# Prototype_PCB.net
KiCad netlist of a schematic drawn in Altium Designer
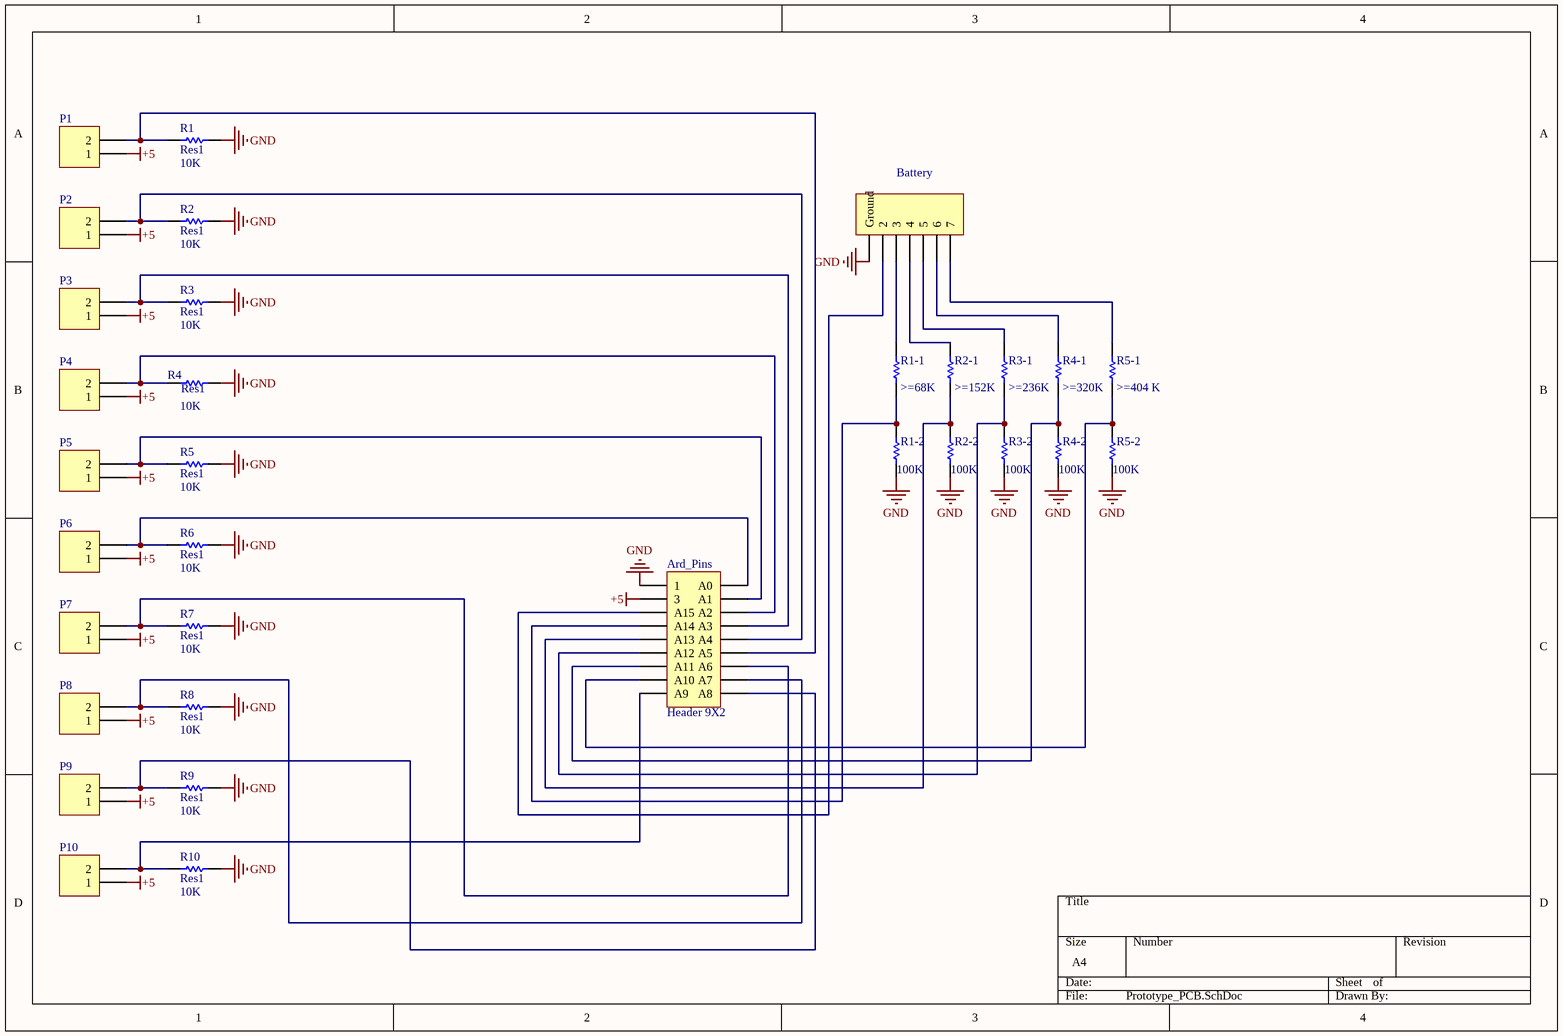
[diagram p0: Prototype_PCB.SchDoc]

(export (version "E")
  (design (tool "Eeschema 10.0.6"))
  (components
    (comp (ref "Ard_Pins")
      (value "Header 9X2")
      (footprint "HDR2X9")
      (description "Header, 9-Pin, Dual row")
      (fields (field (name "PUBLISHER") "Altium Limited"))
      (libsource (lib "Miscellaneous Connectors") (part "Header 9X2"))
    )
    (comp (ref "Battery")
      (value "1")
      (footprint "HDR1X7")
      (description "Header, 7-Pin")
      (fields (field (name "PUBLISHER") "Altium Limited"))
      (libsource (lib "Miscellaneous Connectors") (part "Header 7"))
    )
    (comp (ref "P1")
      (value "MHDR1X2")
      (footprint "MHDR1X2")
      (description "Header, 2-Pin")
      (fields (field (name "PUBLISHER") "Altium Limited"))
      (libsource (lib "Miscellaneous Connectors") (part "MHDR1X2"))
    )
    (comp (ref "P2")
      (value "MHDR1X2")
      (footprint "MHDR1X2")
      (description "Header, 2-Pin")
      (fields (field (name "PUBLISHER") "Altium Limited"))
      (libsource (lib "Miscellaneous Connectors") (part "MHDR1X2"))
    )
    (comp (ref "P3")
      (value "MHDR1X2")
      (footprint "MHDR1X2")
      (description "Header, 2-Pin")
      (fields (field (name "PUBLISHER") "Altium Limited"))
      (libsource (lib "Miscellaneous Connectors") (part "MHDR1X2"))
    )
    (comp (ref "P4")
      (value "MHDR1X2")
      (footprint "MHDR1X2")
      (description "Header, 2-Pin")
      (fields (field (name "PUBLISHER") "Altium Limited"))
      (libsource (lib "Miscellaneous Connectors") (part "MHDR1X2"))
    )
    (comp (ref "P5")
      (value "MHDR1X2")
      (footprint "MHDR1X2")
      (description "Header, 2-Pin")
      (fields (field (name "PUBLISHER") "Altium Limited"))
      (libsource (lib "Miscellaneous Connectors") (part "MHDR1X2"))
    )
    (comp (ref "P6")
      (value "MHDR1X2")
      (footprint "MHDR1X2")
      (description "Header, 2-Pin")
      (fields (field (name "PUBLISHER") "Altium Limited"))
      (libsource (lib "Miscellaneous Connectors") (part "MHDR1X2"))
    )
    (comp (ref "P7")
      (value "MHDR1X2")
      (footprint "MHDR1X2")
      (description "Header, 2-Pin")
      (fields (field (name "PUBLISHER") "Altium Limited"))
      (libsource (lib "Miscellaneous Connectors") (part "MHDR1X2"))
    )
    (comp (ref "P8")
      (value "MHDR1X2")
      (footprint "MHDR1X2")
      (description "Header, 2-Pin")
      (fields (field (name "PUBLISHER") "Altium Limited"))
      (libsource (lib "Miscellaneous Connectors") (part "MHDR1X2"))
    )
    (comp (ref "P9")
      (value "MHDR1X2")
      (footprint "MHDR1X2")
      (description "Header, 2-Pin")
      (fields (field (name "PUBLISHER") "Altium Limited"))
      (libsource (lib "Miscellaneous Connectors") (part "MHDR1X2"))
    )
    (comp (ref "P10")
      (value "MHDR1X2")
      (footprint "MHDR1X2")
      (description "Header, 2-Pin")
      (fields (field (name "PUBLISHER") "Altium Limited"))
      (libsource (lib "Miscellaneous Connectors") (part "MHDR1X2"))
    )
    (comp (ref "R1")
      (value "Res1")
      (footprint "AXIAL-0.3")
      (description "Resistor")
      (fields (field (name "ALTIUM_VALUE") "10K") (field (name "PUBLISHER") "Altium Limited"))
      (libsource (lib "Miscellaneous Devices") (part "Res1"))
    )
    (comp (ref "R1-1")
      (value ">=68K")
      (footprint "AXIAL-0.3")
      (description "Resistor")
      (fields (field (name "Comment") "Res1") (field (name "PUBLISHER") "Altium Limited"))
      (libsource (lib "Miscellaneous Devices") (part "Res1"))
    )
    (comp (ref "R1-2")
      (value "100K")
      (footprint "AXIAL-0.3")
      (description "Resistor")
      (fields (field (name "Comment") "Res1") (field (name "PUBLISHER") "Altium Limited"))
      (libsource (lib "Miscellaneous Devices") (part "Res1"))
    )
    (comp (ref "R2")
      (value "Res1")
      (footprint "AXIAL-0.3")
      (description "Resistor")
      (fields (field (name "ALTIUM_VALUE") "10K") (field (name "PUBLISHER") "Altium Limited"))
      (libsource (lib "Miscellaneous Devices") (part "Res1"))
    )
    (comp (ref "R2-1")
      (value ">=152K")
      (footprint "AXIAL-0.3")
      (description "Resistor")
      (fields (field (name "Comment") "Res1") (field (name "PUBLISHER") "Altium Limited"))
      (libsource (lib "Miscellaneous Devices") (part "Res1"))
    )
    (comp (ref "R2-2")
      (value "100K")
      (footprint "AXIAL-0.3")
      (description "Resistor")
      (fields (field (name "Comment") "Res1") (field (name "PUBLISHER") "Altium Limited"))
      (libsource (lib "Miscellaneous Devices") (part "Res1"))
    )
    (comp (ref "R3")
      (value "Res1")
      (footprint "AXIAL-0.3")
      (description "Resistor")
      (fields (field (name "ALTIUM_VALUE") "10K") (field (name "PUBLISHER") "Altium Limited"))
      (libsource (lib "Miscellaneous Devices") (part "Res1"))
    )
    (comp (ref "R3-1")
      (value ">=236K")
      (footprint "AXIAL-0.3")
      (description "Resistor")
      (fields (field (name "Comment") "Res1") (field (name "PUBLISHER") "Altium Limited"))
      (libsource (lib "Miscellaneous Devices") (part "Res1"))
    )
    (comp (ref "R3-2")
      (value "100K")
      (footprint "AXIAL-0.3")
      (description "Resistor")
      (fields (field (name "Comment") "Res1") (field (name "PUBLISHER") "Altium Limited"))
      (libsource (lib "Miscellaneous Devices") (part "Res1"))
    )
    (comp (ref "R4")
      (value "Res1")
      (footprint "AXIAL-0.3")
      (description "Resistor")
      (fields (field (name "ALTIUM_VALUE") "10K") (field (name "PUBLISHER") "Altium Limited"))
      (libsource (lib "Miscellaneous Devices") (part "Res1"))
    )
    (comp (ref "R4-1")
      (value ">=320K")
      (footprint "AXIAL-0.3")
      (description "Resistor")
      (fields (field (name "Comment") "Res1") (field (name "PUBLISHER") "Altium Limited"))
      (libsource (lib "Miscellaneous Devices") (part "Res1"))
    )
    (comp (ref "R4-2")
      (value "100K")
      (footprint "AXIAL-0.3")
      (description "Resistor")
      (fields (field (name "Comment") "Res1") (field (name "PUBLISHER") "Altium Limited"))
      (libsource (lib "Miscellaneous Devices") (part "Res1"))
    )
    (comp (ref "R5")
      (value "Res1")
      (footprint "AXIAL-0.3")
      (description "Resistor")
      (fields (field (name "ALTIUM_VALUE") "10K") (field (name "PUBLISHER") "Altium Limited"))
      (libsource (lib "Miscellaneous Devices") (part "Res1"))
    )
    (comp (ref "R5-1")
      (value ">=404 K")
      (footprint "AXIAL-0.3")
      (description "Resistor")
      (fields (field (name "Comment") "Res1") (field (name "PUBLISHER") "Altium Limited"))
      (libsource (lib "Miscellaneous Devices") (part "Res1"))
    )
    (comp (ref "R5-2")
      (value "100K")
      (footprint "AXIAL-0.3")
      (description "Resistor")
      (fields (field (name "Comment") "Res1") (field (name "PUBLISHER") "Altium Limited"))
      (libsource (lib "Miscellaneous Devices") (part "Res1"))
    )
    (comp (ref "R6")
      (value "Res1")
      (footprint "AXIAL-0.3")
      (description "Resistor")
      (fields (field (name "ALTIUM_VALUE") "10K") (field (name "PUBLISHER") "Altium Limited"))
      (libsource (lib "Miscellaneous Devices") (part "Res1"))
    )
    (comp (ref "R7")
      (value "Res1")
      (footprint "AXIAL-0.3")
      (description "Resistor")
      (fields (field (name "ALTIUM_VALUE") "10K") (field (name "PUBLISHER") "Altium Limited"))
      (libsource (lib "Miscellaneous Devices") (part "Res1"))
    )
    (comp (ref "R8")
      (value "Res1")
      (footprint "AXIAL-0.3")
      (description "Resistor")
      (fields (field (name "ALTIUM_VALUE") "10K") (field (name "PUBLISHER") "Altium Limited"))
      (libsource (lib "Miscellaneous Devices") (part "Res1"))
    )
    (comp (ref "R9")
      (value "Res1")
      (footprint "AXIAL-0.3")
      (description "Resistor")
      (fields (field (name "ALTIUM_VALUE") "10K") (field (name "PUBLISHER") "Altium Limited"))
      (libsource (lib "Miscellaneous Devices") (part "Res1"))
    )
    (comp (ref "R10")
      (value "Res1")
      (footprint "AXIAL-0.3")
      (description "Resistor")
      (fields (field (name "ALTIUM_VALUE") "10K") (field (name "PUBLISHER") "Altium Limited"))
      (libsource (lib "Miscellaneous Devices") (part "Res1"))
    )
  )
  (nets
    (net (code "1") (name "+5") (class "Default")
      (node (ref "Ard_Pins") (pin "3") (pinfunction "3_3") (pintype "passive"))
      (node (ref "P1") (pin "1") (pinfunction "1_1") (pintype "passive"))
      (node (ref "P10") (pin "1") (pinfunction "1_1") (pintype "passive"))
      (node (ref "P2") (pin "1") (pinfunction "1_1") (pintype "passive"))
      (node (ref "P3") (pin "1") (pinfunction "1_1") (pintype "passive"))
      (node (ref "P4") (pin "1") (pinfunction "1_1") (pintype "passive"))
      (node (ref "P5") (pin "1") (pinfunction "1_1") (pintype "passive"))
      (node (ref "P6") (pin "1") (pinfunction "1_1") (pintype "passive"))
      (node (ref "P7") (pin "1") (pinfunction "1_1") (pintype "passive"))
      (node (ref "P8") (pin "1") (pinfunction "1_1") (pintype "passive"))
      (node (ref "P9") (pin "1") (pinfunction "1_1") (pintype "passive"))
    )
    (net (code "2") (name "GND") (class "Default")
      (node (ref "Ard_Pins") (pin "1") (pinfunction "1_1") (pintype "passive"))
      (node (ref "Battery") (pin "1") (pinfunction "Ground_1") (pintype "passive"))
      (node (ref "R1") (pin "2") (pinfunction "2_2") (pintype "passive"))
      (node (ref "R1-2") (pin "1") (pinfunction "1_1") (pintype "passive"))
      (node (ref "R10") (pin "2") (pinfunction "2_2") (pintype "passive"))
      (node (ref "R2") (pin "2") (pinfunction "2_2") (pintype "passive"))
      (node (ref "R2-2") (pin "1") (pinfunction "1_1") (pintype "passive"))
      (node (ref "R3") (pin "2") (pinfunction "2_2") (pintype "passive"))
      (node (ref "R3-2") (pin "1") (pinfunction "1_1") (pintype "passive"))
      (node (ref "R4") (pin "2") (pinfunction "2_2") (pintype "passive"))
      (node (ref "R4-2") (pin "1") (pinfunction "1_1") (pintype "passive"))
      (node (ref "R5") (pin "2") (pinfunction "2_2") (pintype "passive"))
      (node (ref "R5-2") (pin "1") (pinfunction "1_1") (pintype "passive"))
      (node (ref "R6") (pin "2") (pinfunction "2_2") (pintype "passive"))
      (node (ref "R7") (pin "2") (pinfunction "2_2") (pintype "passive"))
      (node (ref "R8") (pin "2") (pinfunction "2_2") (pintype "passive"))
      (node (ref "R9") (pin "2") (pinfunction "2_2") (pintype "passive"))
    )
    (net (code "3") (name "Net-(Ard_Pins-A0)") (class "Default")
      (node (ref "Ard_Pins") (pin "2") (pinfunction "A0_2") (pintype "passive"))
      (node (ref "P6") (pin "2") (pinfunction "2_2") (pintype "passive"))
      (node (ref "R6") (pin "1") (pinfunction "1_1") (pintype "passive"))
    )
    (net (code "4") (name "Net-(Ard_Pins-A1)") (class "Default")
      (node (ref "Ard_Pins") (pin "4") (pinfunction "A1_4") (pintype "passive"))
      (node (ref "P5") (pin "2") (pinfunction "2_2") (pintype "passive"))
      (node (ref "R5") (pin "1") (pinfunction "1_1") (pintype "passive"))
    )
    (net (code "5") (name "Net-(Ard_Pins-A2)") (class "Default")
      (node (ref "Ard_Pins") (pin "6") (pinfunction "A2_6") (pintype "passive"))
      (node (ref "P4") (pin "2") (pinfunction "2_2") (pintype "passive"))
      (node (ref "R4") (pin "1") (pinfunction "1_1") (pintype "passive"))
    )
    (net (code "6") (name "Net-(Ard_Pins-A3)") (class "Default")
      (node (ref "Ard_Pins") (pin "8") (pinfunction "A3_8") (pintype "passive"))
      (node (ref "P3") (pin "2") (pinfunction "2_2") (pintype "passive"))
      (node (ref "R3") (pin "1") (pinfunction "1_1") (pintype "passive"))
    )
    (net (code "7") (name "Net-(Ard_Pins-A4)") (class "Default")
      (node (ref "Ard_Pins") (pin "10") (pinfunction "A4_10") (pintype "passive"))
      (node (ref "P2") (pin "2") (pinfunction "2_2") (pintype "passive"))
      (node (ref "R2") (pin "1") (pinfunction "1_1") (pintype "passive"))
    )
    (net (code "8") (name "Net-(Ard_Pins-A5)") (class "Default")
      (node (ref "Ard_Pins") (pin "12") (pinfunction "A5_12") (pintype "passive"))
      (node (ref "P1") (pin "2") (pinfunction "2_2") (pintype "passive"))
      (node (ref "R1") (pin "1") (pinfunction "1_1") (pintype "passive"))
    )
    (net (code "9") (name "Net-(Ard_Pins-A6)") (class "Default")
      (node (ref "Ard_Pins") (pin "14") (pinfunction "A6_14") (pintype "passive"))
      (node (ref "P7") (pin "2") (pinfunction "2_2") (pintype "passive"))
      (node (ref "R7") (pin "1") (pinfunction "1_1") (pintype "passive"))
    )
    (net (code "10") (name "Net-(Ard_Pins-A7)") (class "Default")
      (node (ref "Ard_Pins") (pin "16") (pinfunction "A7_16") (pintype "passive"))
      (node (ref "P8") (pin "2") (pinfunction "2_2") (pintype "passive"))
      (node (ref "R8") (pin "1") (pinfunction "1_1") (pintype "passive"))
    )
    (net (code "11") (name "Net-(Ard_Pins-A8)") (class "Default")
      (node (ref "Ard_Pins") (pin "18") (pinfunction "A8_18") (pintype "passive"))
      (node (ref "P9") (pin "2") (pinfunction "2_2") (pintype "passive"))
      (node (ref "R9") (pin "1") (pinfunction "1_1") (pintype "passive"))
    )
    (net (code "12") (name "Net-(Ard_Pins-A9)") (class "Default")
      (node (ref "Ard_Pins") (pin "17") (pinfunction "A9_17") (pintype "passive"))
      (node (ref "P10") (pin "2") (pinfunction "2_2") (pintype "passive"))
      (node (ref "R10") (pin "1") (pinfunction "1_1") (pintype "passive"))
    )
    (net (code "13") (name "Net-(Ard_Pins-A10)") (class "Default")
      (node (ref "Ard_Pins") (pin "15") (pinfunction "A10_15") (pintype "passive"))
      (node (ref "R5-1") (pin "1") (pinfunction "1_1") (pintype "passive"))
      (node (ref "R5-2") (pin "2") (pinfunction "2_2") (pintype "passive"))
    )
    (net (code "14") (name "Net-(Ard_Pins-A11)") (class "Default")
      (node (ref "Ard_Pins") (pin "13") (pinfunction "A11_13") (pintype "passive"))
      (node (ref "R4-1") (pin "1") (pinfunction "1_1") (pintype "passive"))
      (node (ref "R4-2") (pin "2") (pinfunction "2_2") (pintype "passive"))
    )
    (net (code "15") (name "Net-(Ard_Pins-A12)") (class "Default")
      (node (ref "Ard_Pins") (pin "11") (pinfunction "A12_11") (pintype "passive"))
      (node (ref "R3-1") (pin "1") (pinfunction "1_1") (pintype "passive"))
      (node (ref "R3-2") (pin "2") (pinfunction "2_2") (pintype "passive"))
    )
    (net (code "16") (name "Net-(Ard_Pins-A13)") (class "Default")
      (node (ref "Ard_Pins") (pin "9") (pinfunction "A13_9") (pintype "passive"))
      (node (ref "R2-1") (pin "1") (pinfunction "1_1") (pintype "passive"))
      (node (ref "R2-2") (pin "2") (pinfunction "2_2") (pintype "passive"))
    )
    (net (code "17") (name "Net-(Ard_Pins-A14)") (class "Default")
      (node (ref "Ard_Pins") (pin "7") (pinfunction "A14_7") (pintype "passive"))
      (node (ref "R1-1") (pin "1") (pinfunction "1_1") (pintype "passive"))
      (node (ref "R1-2") (pin "2") (pinfunction "2_2") (pintype "passive"))
    )
    (net (code "18") (name "Net-(Ard_Pins-A15)") (class "Default")
      (node (ref "Ard_Pins") (pin "5") (pinfunction "A15_5") (pintype "passive"))
      (node (ref "Battery") (pin "2") (pinfunction "2_2") (pintype "passive"))
    )
    (net (code "19") (name "Net-(Battery-Pad3)") (class "Default")
      (node (ref "Battery") (pin "3") (pinfunction "3_3") (pintype "passive"))
      (node (ref "R1-1") (pin "2") (pinfunction "2_2") (pintype "passive"))
    )
    (net (code "20") (name "Net-(Battery-Pad4)") (class "Default")
      (node (ref "Battery") (pin "4") (pinfunction "4_4") (pintype "passive"))
      (node (ref "R2-1") (pin "2") (pinfunction "2_2") (pintype "passive"))
    )
    (net (code "21") (name "Net-(Battery-Pad5)") (class "Default")
      (node (ref "Battery") (pin "5") (pinfunction "5_5") (pintype "passive"))
      (node (ref "R3-1") (pin "2") (pinfunction "2_2") (pintype "passive"))
    )
    (net (code "22") (name "Net-(Battery-Pad6)") (class "Default")
      (node (ref "Battery") (pin "6") (pinfunction "6_6") (pintype "passive"))
      (node (ref "R4-1") (pin "2") (pinfunction "2_2") (pintype "passive"))
    )
    (net (code "23") (name "Net-(Battery-Pad7)") (class "Default")
      (node (ref "Battery") (pin "7") (pinfunction "7_7") (pintype "passive"))
      (node (ref "R5-1") (pin "2") (pinfunction "2_2") (pintype "passive"))
    )
  )
)
